# MCU_AVR_ATmega2560-16AU.net
KiCad netlist of a schematic drawn in Altium Designer
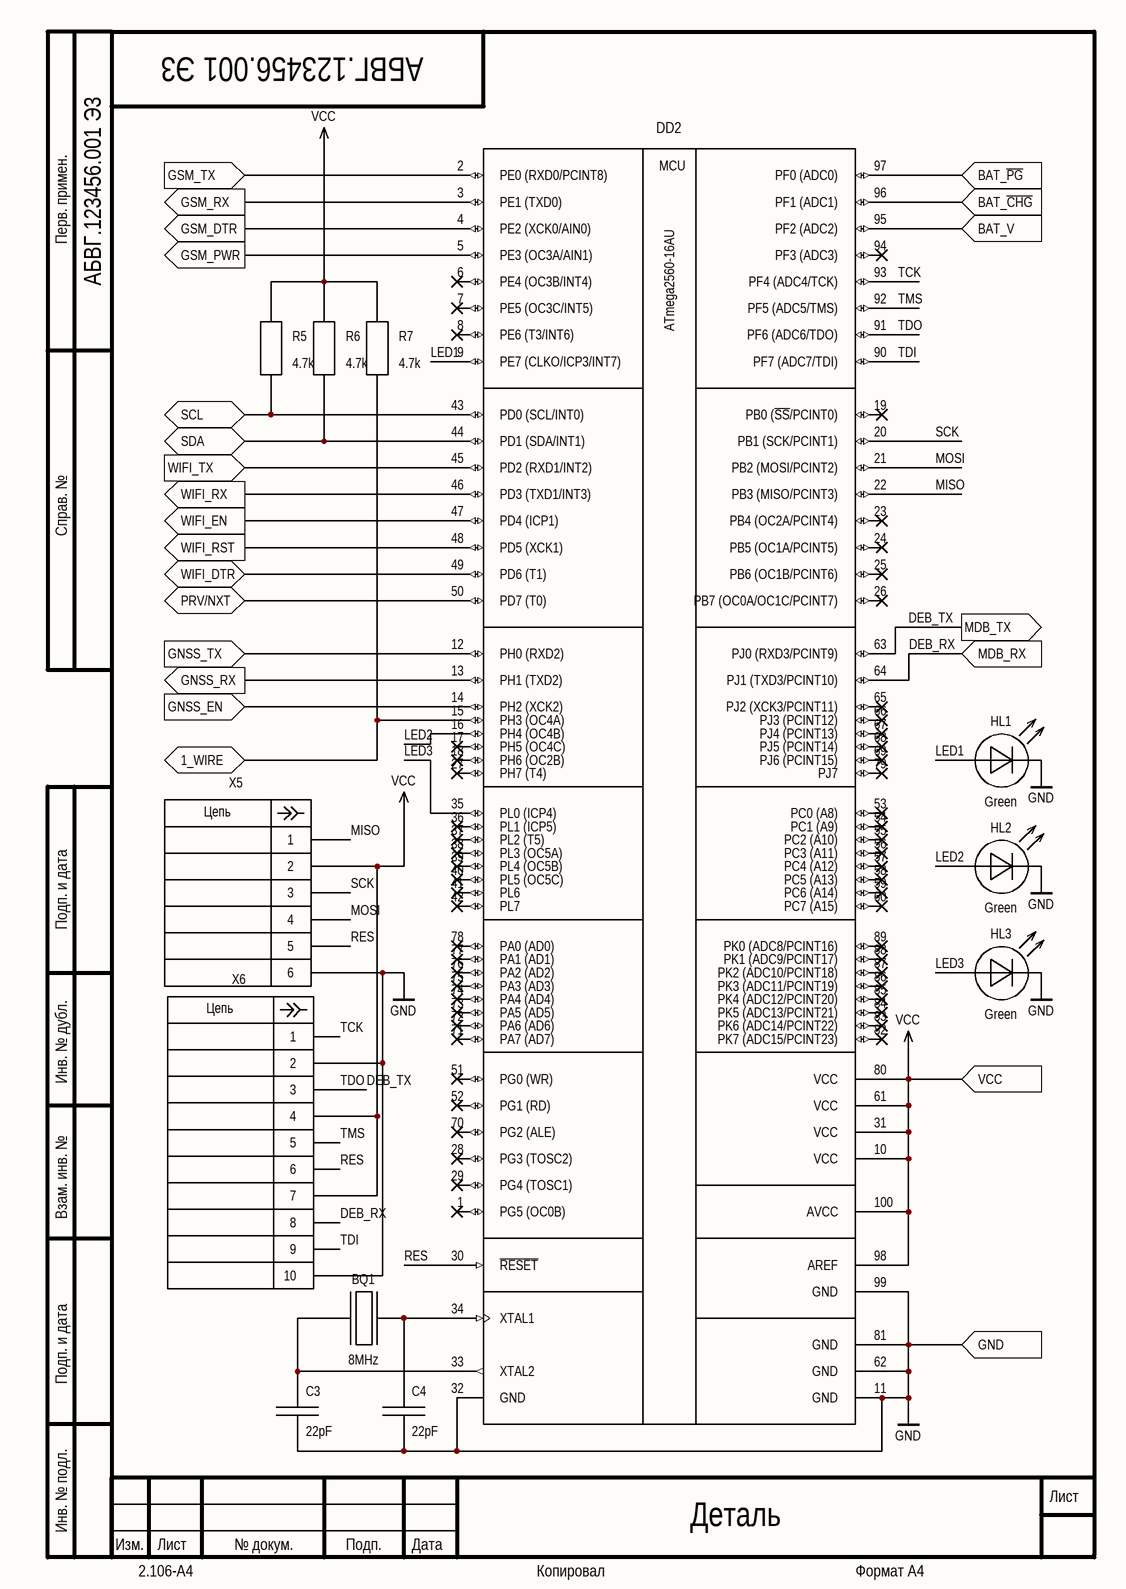
[diagram p0: MCU AVR ATmega2560-16AU.SchDoc]

(export (version "E")
  (design (tool "Eeschema 10.0.6"))
  (components
    (comp (ref "BQ1")
      (value "8MHz")
      (footprint "HC-49S")
      (description "Crystal 8MHz")
      (fields (field (name "MANUFACTURER") "TXC CORPORATION"))
      (libsource (lib "Discrete components") (part "9B08000037"))
    )
    (comp (ref "C3")
      (value "22pF")
      (footprint "CAPC1608L")
      (description "Capacitor Ceramic 22pF 50V 0603(1608)")
      (fields (field (name "TOLERANCE") "±5%") (field (name "MANUFACTURER") "Yageo"))
      (libsource (lib "Capacitors") (part "CC0201JRNPO9BN220"))
    )
    (comp (ref "C4")
      (value "22pF")
      (footprint "CAPC1608L")
      (description "Capacitor Ceramic 22pF 50V 0603(1608)")
      (fields (field (name "TOLERANCE") "±5%") (field (name "MANUFACTURER") "Yageo"))
      (libsource (lib "Capacitors") (part "CC0201JRNPO9BN220"))
    )
    (comp (ref "DD2")
      (value "ATmega2560-16AU")
      (footprint "TQFP-100N")
      (description "MCU MEGA")
      (fields (field (name "MANUFACTURER") "Atmel"))
      (libsource (lib "ICs") (part "ATmega2560-16AU"))
    )
    (comp (ref "HL1")
      (value "Green")
      (footprint "LED 2012N")
      (description "LED")
      (fields (field (name "MANUFACTURER") "OSRAM Opto Semiconductors Inc."))
      (libsource (lib "Optical") (part "LED 2012"))
    )
    (comp (ref "HL2")
      (value "Green")
      (footprint "LED 2012N")
      (description "LED")
      (fields (field (name "MANUFACTURER") "OSRAM Opto Semiconductors Inc."))
      (libsource (lib "Optical") (part "LED 2012"))
    )
    (comp (ref "HL3")
      (value "Green")
      (footprint "LED 2012N")
      (description "LED")
      (fields (field (name "MANUFACTURER") "OSRAM Opto Semiconductors Inc."))
      (libsource (lib "Optical") (part "LED 2012"))
    )
    (comp (ref "R5")
      (value "4.7k")
      (footprint "RESC1608L")
      (description "Resistor Ceramic 4.7k 0.1W 0603(1608)")
      (fields (field (name "MANUFACTURER") "Yageo") (field (name "TOLERANCE") "±5%"))
      (libsource (lib "Resistors") (part "RC0603JR-074K7L"))
    )
    (comp (ref "R6")
      (value "4.7k")
      (footprint "RESC1608L")
      (description "Resistor Ceramic 4.7k 0.1W 0603(1608)")
      (fields (field (name "MANUFACTURER") "Yageo") (field (name "TOLERANCE") "±5%"))
      (libsource (lib "Resistors") (part "RC0603JR-074K7L"))
    )
    (comp (ref "R7")
      (value "4.7k")
      (footprint "RESC1608L")
      (description "Resistor Ceramic 4.7k 0.1W 0603(1608)")
      (fields (field (name "MANUFACTURER") "Yageo") (field (name "TOLERANCE") "±5%"))
      (libsource (lib "Resistors") (part "RC0603JR-074K7L"))
    )
    (comp (ref "X5")
      (value "Atmel ISP connector")
      (footprint "Atmel ISP")
      (description "Debug Atmel ISP Pads")
      (fields (field (name "MANUFACTURER") "Atmel"))
      (libsource (lib "Connectors") (part "Atmel ISP connector"))
    )
    (comp (ref "X6")
      (value "Atmel ICE AVR JTAG connector")
      (footprint "Atmel ICE Connector")
      (description "Debug AVR JTAG ICE Pads")
      (fields (field (name "MANUFACTURER") "Atmel"))
      (libsource (lib "Connectors") (part "Atmel ICE AVR JTAG connector"))
    )
  )
  (nets
    (net (code "1") (name "/1_WIRE") (class "Default")
      (node (ref "DD2") (pin "15") (pinfunction "PH3_(OC4A)_15") (pintype "bidirectional"))
      (node (ref "R7") (pin "2") (pinfunction "2_2") (pintype "passive"))
    )
    (net (code "2") (name "/BAT_V") (class "Default")
      (node (ref "DD2") (pin "95") (pinfunction "PF2_(ADC2)_95") (pintype "bidirectional"))
    )
    (net (code "3") (name "/BAT_~{CHG}") (class "Default")
      (node (ref "DD2") (pin "96") (pinfunction "PF1_(ADC1)_96") (pintype "bidirectional"))
    )
    (net (code "4") (name "/BAT_~{PG}") (class "Default")
      (node (ref "DD2") (pin "97") (pinfunction "PF0_(ADC0)_97") (pintype "bidirectional"))
    )
    (net (code "5") (name "/DEB_RX") (class "Default")
      (node (ref "DD2") (pin "64") (pinfunction "PJ1_(TXD3/PCINT10)_64") (pintype "bidirectional"))
      (node (ref "X6") (pin "8") (pinfunction "8_8") (pintype "passive"))
    )
    (net (code "6") (name "/DEB_TX") (class "Default")
      (node (ref "DD2") (pin "63") (pinfunction "PJ0_(RXD3/PCINT9)_63") (pintype "bidirectional"))
      (node (ref "DD2") (pin "91") (pinfunction "PF6_(ADC6/TDO)_91") (pintype "bidirectional"))
      (node (ref "X6") (pin "3") (pinfunction "3_3") (pintype "passive"))
    )
    (net (code "7") (name "/GNSS_EN") (class "Default")
      (node (ref "DD2") (pin "14") (pinfunction "PH2_(XCK2)_14") (pintype "bidirectional"))
    )
    (net (code "8") (name "/GNSS_RX") (class "Default")
      (node (ref "DD2") (pin "13") (pinfunction "PH1_(TXD2)_13") (pintype "bidirectional"))
    )
    (net (code "9") (name "/GNSS_TX") (class "Default")
      (node (ref "DD2") (pin "12") (pinfunction "PH0_(RXD2)_12") (pintype "bidirectional"))
    )
    (net (code "10") (name "/GSM_DTR") (class "Default")
      (node (ref "DD2") (pin "4") (pinfunction "PE2_(XCK0/AIN0)_4") (pintype "bidirectional"))
    )
    (net (code "11") (name "/GSM_PWR") (class "Default")
      (node (ref "DD2") (pin "5") (pinfunction "PE3_(OC3A/AIN1)_5") (pintype "bidirectional"))
    )
    (net (code "12") (name "/GSM_RX") (class "Default")
      (node (ref "DD2") (pin "3") (pinfunction "PE1_(TXD0)_3") (pintype "bidirectional"))
    )
    (net (code "13") (name "/GSM_TX") (class "Default")
      (node (ref "DD2") (pin "2") (pinfunction "PE0_(RXD0/PCINT8)_2") (pintype "bidirectional"))
    )
    (net (code "14") (name "/LED1") (class "Default")
      (node (ref "DD2") (pin "9") (pinfunction "PE7_(CLKO/ICP3/INT7)_9") (pintype "bidirectional"))
      (node (ref "HL1") (pin "1") (pinfunction "Anode_1") (pintype "passive"))
    )
    (net (code "15") (name "/LED2") (class "Default")
      (node (ref "DD2") (pin "16") (pinfunction "PH4_(OC4B)_16") (pintype "bidirectional"))
      (node (ref "HL2") (pin "1") (pinfunction "Anode_1") (pintype "passive"))
    )
    (net (code "16") (name "/LED3") (class "Default")
      (node (ref "DD2") (pin "35") (pinfunction "PL0_(ICP4)_35") (pintype "bidirectional"))
      (node (ref "HL3") (pin "1") (pinfunction "Anode_1") (pintype "passive"))
    )
    (net (code "17") (name "/MISO") (class "Default")
      (node (ref "DD2") (pin "22") (pinfunction "PB3_(MISO/PCINT3)_22") (pintype "bidirectional"))
      (node (ref "X5") (pin "1") (pinfunction "1_1") (pintype "passive"))
    )
    (net (code "18") (name "/MOSI") (class "Default")
      (node (ref "DD2") (pin "21") (pinfunction "PB2_(MOSI/PCINT2)_21") (pintype "bidirectional"))
      (node (ref "X5") (pin "4") (pinfunction "4_4") (pintype "passive"))
    )
    (net (code "19") (name "/PRV{slash}NXT") (class "Default")
      (node (ref "DD2") (pin "50") (pinfunction "PD7_(T0)_50") (pintype "bidirectional"))
    )
    (net (code "20") (name "/RES") (class "Default")
      (node (ref "DD2") (pin "30") (pinfunction "~{RESET}_30") (pintype "input"))
      (node (ref "X5") (pin "5") (pinfunction "5_5") (pintype "passive"))
      (node (ref "X6") (pin "6") (pinfunction "6_6") (pintype "passive"))
    )
    (net (code "21") (name "/SCK") (class "Default")
      (node (ref "DD2") (pin "20") (pinfunction "PB1_(SCK/PCINT1)_20") (pintype "bidirectional"))
      (node (ref "X5") (pin "3") (pinfunction "3_3") (pintype "passive"))
    )
    (net (code "22") (name "/SCL") (class "Default")
      (node (ref "DD2") (pin "43") (pinfunction "PD0_(SCL/INT0)_43") (pintype "bidirectional"))
      (node (ref "R5") (pin "2") (pinfunction "2_2") (pintype "passive"))
    )
    (net (code "23") (name "/SDA") (class "Default")
      (node (ref "DD2") (pin "44") (pinfunction "PD1_(SDA/INT1)_44") (pintype "bidirectional"))
      (node (ref "R6") (pin "2") (pinfunction "2_2") (pintype "passive"))
    )
    (net (code "24") (name "/TCK") (class "Default")
      (node (ref "DD2") (pin "93") (pinfunction "PF4_(ADC4/TCK)_93") (pintype "bidirectional"))
      (node (ref "X6") (pin "1") (pinfunction "1_1") (pintype "passive"))
    )
    (net (code "25") (name "/TDI") (class "Default")
      (node (ref "DD2") (pin "90") (pinfunction "PF7_(ADC7/TDI)_90") (pintype "bidirectional"))
      (node (ref "X6") (pin "9") (pinfunction "9_9") (pintype "passive"))
    )
    (net (code "26") (name "/TMS") (class "Default")
      (node (ref "DD2") (pin "92") (pinfunction "PF5_(ADC5/TMS)_92") (pintype "bidirectional"))
      (node (ref "X6") (pin "5") (pinfunction "5_5") (pintype "passive"))
    )
    (net (code "27") (name "/WIFI_DTR") (class "Default")
      (node (ref "DD2") (pin "49") (pinfunction "PD6_(T1)_49") (pintype "bidirectional"))
    )
    (net (code "28") (name "/WIFI_EN") (class "Default")
      (node (ref "DD2") (pin "47") (pinfunction "PD4_(ICP1)_47") (pintype "bidirectional"))
    )
    (net (code "29") (name "/WIFI_RST") (class "Default")
      (node (ref "DD2") (pin "48") (pinfunction "PD5_(XCK1)_48") (pintype "bidirectional"))
    )
    (net (code "30") (name "/WIFI_RX") (class "Default")
      (node (ref "DD2") (pin "46") (pinfunction "PD3_(TXD1/INT3)_46") (pintype "bidirectional"))
    )
    (net (code "31") (name "/WIFI_TX") (class "Default")
      (node (ref "DD2") (pin "45") (pinfunction "PD2_(RXD1/INT2)_45") (pintype "bidirectional"))
    )
    (net (code "32") (name "GND") (class "Default")
      (node (ref "C3") (pin "2") (pinfunction "2_2") (pintype "passive"))
      (node (ref "C4") (pin "2") (pinfunction "2_2") (pintype "passive"))
      (node (ref "DD2") (pin "11") (pinfunction "GND_11") (pintype "power_in"))
      (node (ref "DD2") (pin "32") (pinfunction "GND_32") (pintype "power_in"))
      (node (ref "DD2") (pin "62") (pinfunction "GND_62") (pintype "power_in"))
      (node (ref "DD2") (pin "81") (pinfunction "GND_81") (pintype "power_in"))
      (node (ref "DD2") (pin "99") (pinfunction "GND_99") (pintype "power_in"))
      (node (ref "HL1") (pin "2") (pinfunction "Cathode_2") (pintype "passive"))
      (node (ref "HL2") (pin "2") (pinfunction "Cathode_2") (pintype "passive"))
      (node (ref "HL3") (pin "2") (pinfunction "Cathode_2") (pintype "passive"))
      (node (ref "X5") (pin "6") (pinfunction "6_6") (pintype "passive"))
      (node (ref "X6") (pin "10") (pinfunction "10_10") (pintype "passive"))
      (node (ref "X6") (pin "2") (pinfunction "2_2") (pintype "passive"))
    )
    (net (code "33") (name "Net-(DD2-XTAL1)") (class "Default")
      (node (ref "BQ1") (pin "2") (pinfunction "2_2") (pintype "passive"))
      (node (ref "C4") (pin "1") (pinfunction "1_1") (pintype "passive"))
      (node (ref "DD2") (pin "34") (pinfunction "XTAL1_34") (pintype "input"))
    )
    (net (code "34") (name "Net-(DD2-XTAL2)") (class "Default")
      (node (ref "BQ1") (pin "1") (pinfunction "1_1") (pintype "passive"))
      (node (ref "C3") (pin "1") (pinfunction "1_1") (pintype "passive"))
      (node (ref "DD2") (pin "33") (pinfunction "XTAL2_33") (pintype "output"))
    )
    (net (code "35") (name "VCC") (class "Default")
      (node (ref "DD2") (pin "10") (pinfunction "VCC_10") (pintype "power_in"))
      (node (ref "DD2") (pin "100") (pinfunction "AVCC_100") (pintype "power_in"))
      (node (ref "DD2") (pin "31") (pinfunction "VCC_31") (pintype "power_in"))
      (node (ref "DD2") (pin "61") (pinfunction "VCC_61") (pintype "power_in"))
      (node (ref "DD2") (pin "80") (pinfunction "VCC_80") (pintype "power_in"))
      (node (ref "DD2") (pin "98") (pinfunction "AREF_98") (pintype "power_in"))
      (node (ref "R5") (pin "1") (pinfunction "1_1") (pintype "passive"))
      (node (ref "R6") (pin "1") (pinfunction "1_1") (pintype "passive"))
      (node (ref "R7") (pin "1") (pinfunction "1_1") (pintype "passive"))
      (node (ref "X5") (pin "2") (pinfunction "2_2") (pintype "passive"))
      (node (ref "X6") (pin "4") (pinfunction "4_4") (pintype "passive"))
      (node (ref "X6") (pin "7") (pinfunction "7_7") (pintype "passive"))
    )
    (net (code "36") (name "unconnected-(DD2-PA0_(AD0)-Pad78)") (class "Default")
      (node (ref "DD2") (pin "78") (pinfunction "PA0_(AD0)_78") (pintype "bidirectional+no_connect"))
    )
    (net (code "37") (name "unconnected-(DD2-PA1_(AD1)-Pad77)") (class "Default")
      (node (ref "DD2") (pin "77") (pinfunction "PA1_(AD1)_77") (pintype "bidirectional+no_connect"))
    )
    (net (code "38") (name "unconnected-(DD2-PA2_(AD2)-Pad76)") (class "Default")
      (node (ref "DD2") (pin "76") (pinfunction "PA2_(AD2)_76") (pintype "bidirectional+no_connect"))
    )
    (net (code "39") (name "unconnected-(DD2-PA3_(AD3)-Pad75)") (class "Default")
      (node (ref "DD2") (pin "75") (pinfunction "PA3_(AD3)_75") (pintype "bidirectional+no_connect"))
    )
    (net (code "40") (name "unconnected-(DD2-PA4_(AD4)-Pad74)") (class "Default")
      (node (ref "DD2") (pin "74") (pinfunction "PA4_(AD4)_74") (pintype "bidirectional+no_connect"))
    )
    (net (code "41") (name "unconnected-(DD2-PA5_(AD5)-Pad73)") (class "Default")
      (node (ref "DD2") (pin "73") (pinfunction "PA5_(AD5)_73") (pintype "bidirectional+no_connect"))
    )
    (net (code "42") (name "unconnected-(DD2-PA6_(AD6)-Pad72)") (class "Default")
      (node (ref "DD2") (pin "72") (pinfunction "PA6_(AD6)_72") (pintype "bidirectional+no_connect"))
    )
    (net (code "43") (name "unconnected-(DD2-PA7_(AD7)-Pad71)") (class "Default")
      (node (ref "DD2") (pin "71") (pinfunction "PA7_(AD7)_71") (pintype "bidirectional+no_connect"))
    )
    (net (code "44") (name "unconnected-(DD2-PB0_(~{SS}{slash}PCINT0)-Pad19)") (class "Default")
      (node (ref "DD2") (pin "19") (pinfunction "PB0_(~{SS}/PCINT0)_19") (pintype "bidirectional+no_connect"))
    )
    (net (code "45") (name "unconnected-(DD2-PB4_(OC2A{slash}PCINT4)-Pad23)") (class "Default")
      (node (ref "DD2") (pin "23") (pinfunction "PB4_(OC2A/PCINT4)_23") (pintype "bidirectional+no_connect"))
    )
    (net (code "46") (name "unconnected-(DD2-PB5_(OC1A{slash}PCINT5)-Pad24)") (class "Default")
      (node (ref "DD2") (pin "24") (pinfunction "PB5_(OC1A/PCINT5)_24") (pintype "bidirectional+no_connect"))
    )
    (net (code "47") (name "unconnected-(DD2-PB6_(OC1B{slash}PCINT6)-Pad25)") (class "Default")
      (node (ref "DD2") (pin "25") (pinfunction "PB6_(OC1B/PCINT6)_25") (pintype "bidirectional+no_connect"))
    )
    (net (code "48") (name "unconnected-(DD2-PB7_(OC0A{slash}OC1C{slash}PCINT7)-Pad26)") (class "Default")
      (node (ref "DD2") (pin "26") (pinfunction "PB7_(OC0A/OC1C/PCINT7)_26") (pintype "bidirectional+no_connect"))
    )
    (net (code "49") (name "unconnected-(DD2-PC0_(A8)-Pad53)") (class "Default")
      (node (ref "DD2") (pin "53") (pinfunction "PC0_(A8)_53") (pintype "bidirectional+no_connect"))
    )
    (net (code "50") (name "unconnected-(DD2-PC1_(A9)-Pad54)") (class "Default")
      (node (ref "DD2") (pin "54") (pinfunction "PC1_(A9)_54") (pintype "bidirectional+no_connect"))
    )
    (net (code "51") (name "unconnected-(DD2-PC2_(A10)-Pad55)") (class "Default")
      (node (ref "DD2") (pin "55") (pinfunction "PC2_(A10)_55") (pintype "bidirectional+no_connect"))
    )
    (net (code "52") (name "unconnected-(DD2-PC3_(A11)-Pad56)") (class "Default")
      (node (ref "DD2") (pin "56") (pinfunction "PC3_(A11)_56") (pintype "bidirectional+no_connect"))
    )
    (net (code "53") (name "unconnected-(DD2-PC4_(A12)-Pad57)") (class "Default")
      (node (ref "DD2") (pin "57") (pinfunction "PC4_(A12)_57") (pintype "bidirectional+no_connect"))
    )
    (net (code "54") (name "unconnected-(DD2-PC5_(A13)-Pad58)") (class "Default")
      (node (ref "DD2") (pin "58") (pinfunction "PC5_(A13)_58") (pintype "bidirectional+no_connect"))
    )
    (net (code "55") (name "unconnected-(DD2-PC6_(A14)-Pad59)") (class "Default")
      (node (ref "DD2") (pin "59") (pinfunction "PC6_(A14)_59") (pintype "bidirectional+no_connect"))
    )
    (net (code "56") (name "unconnected-(DD2-PC7_(A15)-Pad60)") (class "Default")
      (node (ref "DD2") (pin "60") (pinfunction "PC7_(A15)_60") (pintype "bidirectional+no_connect"))
    )
    (net (code "57") (name "unconnected-(DD2-PE4_(OC3B{slash}INT4)-Pad6)") (class "Default")
      (node (ref "DD2") (pin "6") (pinfunction "PE4_(OC3B/INT4)_6") (pintype "bidirectional+no_connect"))
    )
    (net (code "58") (name "unconnected-(DD2-PE5_(OC3C{slash}INT5)-Pad7)") (class "Default")
      (node (ref "DD2") (pin "7") (pinfunction "PE5_(OC3C/INT5)_7") (pintype "bidirectional+no_connect"))
    )
    (net (code "59") (name "unconnected-(DD2-PE6_(T3{slash}INT6)-Pad8)") (class "Default")
      (node (ref "DD2") (pin "8") (pinfunction "PE6_(T3/INT6)_8") (pintype "bidirectional+no_connect"))
    )
    (net (code "60") (name "unconnected-(DD2-PF3_(ADC3)-Pad94)") (class "Default")
      (node (ref "DD2") (pin "94") (pinfunction "PF3_(ADC3)_94") (pintype "bidirectional+no_connect"))
    )
    (net (code "61") (name "unconnected-(DD2-PG0_(WR)-Pad51)") (class "Default")
      (node (ref "DD2") (pin "51") (pinfunction "PG0_(WR)_51") (pintype "bidirectional+no_connect"))
    )
    (net (code "62") (name "unconnected-(DD2-PG1_(RD)-Pad52)") (class "Default")
      (node (ref "DD2") (pin "52") (pinfunction "PG1_(RD)_52") (pintype "bidirectional+no_connect"))
    )
    (net (code "63") (name "unconnected-(DD2-PG2_(ALE)-Pad70)") (class "Default")
      (node (ref "DD2") (pin "70") (pinfunction "PG2_(ALE)_70") (pintype "bidirectional+no_connect"))
    )
    (net (code "64") (name "unconnected-(DD2-PG3_(TOSC2)-Pad28)") (class "Default")
      (node (ref "DD2") (pin "28") (pinfunction "PG3_(TOSC2)_28") (pintype "bidirectional+no_connect"))
    )
    (net (code "65") (name "unconnected-(DD2-PG4_(TOSC1)-Pad29)") (class "Default")
      (node (ref "DD2") (pin "29") (pinfunction "PG4_(TOSC1)_29") (pintype "bidirectional+no_connect"))
    )
    (net (code "66") (name "unconnected-(DD2-PG5_(OC0B)-Pad1)") (class "Default")
      (node (ref "DD2") (pin "1") (pinfunction "PG5_(OC0B)_1") (pintype "bidirectional+no_connect"))
    )
    (net (code "67") (name "unconnected-(DD2-PH5_(OC4C)-Pad17)") (class "Default")
      (node (ref "DD2") (pin "17") (pinfunction "PH5_(OC4C)_17") (pintype "bidirectional+no_connect"))
    )
    (net (code "68") (name "unconnected-(DD2-PH6_(OC2B)-Pad18)") (class "Default")
      (node (ref "DD2") (pin "18") (pinfunction "PH6_(OC2B)_18") (pintype "bidirectional+no_connect"))
    )
    (net (code "69") (name "unconnected-(DD2-PH7_(T4)-Pad27)") (class "Default")
      (node (ref "DD2") (pin "27") (pinfunction "PH7_(T4)_27") (pintype "bidirectional+no_connect"))
    )
    (net (code "70") (name "unconnected-(DD2-PJ2_(XCK3{slash}PCINT11)-Pad65)") (class "Default")
      (node (ref "DD2") (pin "65") (pinfunction "PJ2_(XCK3/PCINT11)_65") (pintype "bidirectional+no_connect"))
    )
    (net (code "71") (name "unconnected-(DD2-PJ3_(PCINT12)-Pad66)") (class "Default")
      (node (ref "DD2") (pin "66") (pinfunction "PJ3_(PCINT12)_66") (pintype "bidirectional+no_connect"))
    )
    (net (code "72") (name "unconnected-(DD2-PJ4_(PCINT13)-Pad67)") (class "Default")
      (node (ref "DD2") (pin "67") (pinfunction "PJ4_(PCINT13)_67") (pintype "bidirectional+no_connect"))
    )
    (net (code "73") (name "unconnected-(DD2-PJ5_(PCINT14)-Pad68)") (class "Default")
      (node (ref "DD2") (pin "68") (pinfunction "PJ5_(PCINT14)_68") (pintype "bidirectional+no_connect"))
    )
    (net (code "74") (name "unconnected-(DD2-PJ6_(PCINT15)-Pad69)") (class "Default")
      (node (ref "DD2") (pin "69") (pinfunction "PJ6_(PCINT15)_69") (pintype "bidirectional+no_connect"))
    )
    (net (code "75") (name "unconnected-(DD2-PJ7-Pad79)") (class "Default")
      (node (ref "DD2") (pin "79") (pinfunction "PJ7_79") (pintype "bidirectional+no_connect"))
    )
    (net (code "76") (name "unconnected-(DD2-PK0_(ADC8{slash}PCINT16)-Pad89)") (class "Default")
      (node (ref "DD2") (pin "89") (pinfunction "PK0_(ADC8/PCINT16)_89") (pintype "bidirectional+no_connect"))
    )
    (net (code "77") (name "unconnected-(DD2-PK1_(ADC9{slash}PCINT17)-Pad88)") (class "Default")
      (node (ref "DD2") (pin "88") (pinfunction "PK1_(ADC9/PCINT17)_88") (pintype "bidirectional+no_connect"))
    )
    (net (code "78") (name "unconnected-(DD2-PK2_(ADC10{slash}PCINT18)-Pad87)") (class "Default")
      (node (ref "DD2") (pin "87") (pinfunction "PK2_(ADC10/PCINT18)_87") (pintype "bidirectional+no_connect"))
    )
    (net (code "79") (name "unconnected-(DD2-PK3_(ADC11{slash}PCINT19)-Pad86)") (class "Default")
      (node (ref "DD2") (pin "86") (pinfunction "PK3_(ADC11/PCINT19)_86") (pintype "bidirectional+no_connect"))
    )
    (net (code "80") (name "unconnected-(DD2-PK4_(ADC12{slash}PCINT20)-Pad85)") (class "Default")
      (node (ref "DD2") (pin "85") (pinfunction "PK4_(ADC12/PCINT20)_85") (pintype "bidirectional+no_connect"))
    )
    (net (code "81") (name "unconnected-(DD2-PK5_(ADC13{slash}PCINT21)-Pad84)") (class "Default")
      (node (ref "DD2") (pin "84") (pinfunction "PK5_(ADC13/PCINT21)_84") (pintype "bidirectional+no_connect"))
    )
    (net (code "82") (name "unconnected-(DD2-PK6_(ADC14{slash}PCINT22)-Pad83)") (class "Default")
      (node (ref "DD2") (pin "83") (pinfunction "PK6_(ADC14/PCINT22)_83") (pintype "bidirectional+no_connect"))
    )
    (net (code "83") (name "unconnected-(DD2-PK7_(ADC15{slash}PCINT23)-Pad82)") (class "Default")
      (node (ref "DD2") (pin "82") (pinfunction "PK7_(ADC15/PCINT23)_82") (pintype "bidirectional+no_connect"))
    )
    (net (code "84") (name "unconnected-(DD2-PL1_(ICP5)-Pad36)") (class "Default")
      (node (ref "DD2") (pin "36") (pinfunction "PL1_(ICP5)_36") (pintype "bidirectional+no_connect"))
    )
    (net (code "85") (name "unconnected-(DD2-PL2_(T5)-Pad37)") (class "Default")
      (node (ref "DD2") (pin "37") (pinfunction "PL2_(T5)_37") (pintype "bidirectional+no_connect"))
    )
    (net (code "86") (name "unconnected-(DD2-PL3_(OC5A)-Pad38)") (class "Default")
      (node (ref "DD2") (pin "38") (pinfunction "PL3_(OC5A)_38") (pintype "bidirectional+no_connect"))
    )
    (net (code "87") (name "unconnected-(DD2-PL4_(OC5B)-Pad39)") (class "Default")
      (node (ref "DD2") (pin "39") (pinfunction "PL4_(OC5B)_39") (pintype "bidirectional+no_connect"))
    )
    (net (code "88") (name "unconnected-(DD2-PL5_(OC5C)-Pad40)") (class "Default")
      (node (ref "DD2") (pin "40") (pinfunction "PL5_(OC5C)_40") (pintype "bidirectional+no_connect"))
    )
    (net (code "89") (name "unconnected-(DD2-PL6-Pad41)") (class "Default")
      (node (ref "DD2") (pin "41") (pinfunction "PL6_41") (pintype "bidirectional+no_connect"))
    )
    (net (code "90") (name "unconnected-(DD2-PL7-Pad42)") (class "Default")
      (node (ref "DD2") (pin "42") (pinfunction "PL7_42") (pintype "bidirectional+no_connect"))
    )
  )
)
